# sensor_v4.net
KiCad netlist of a schematic drawn in EAGLE
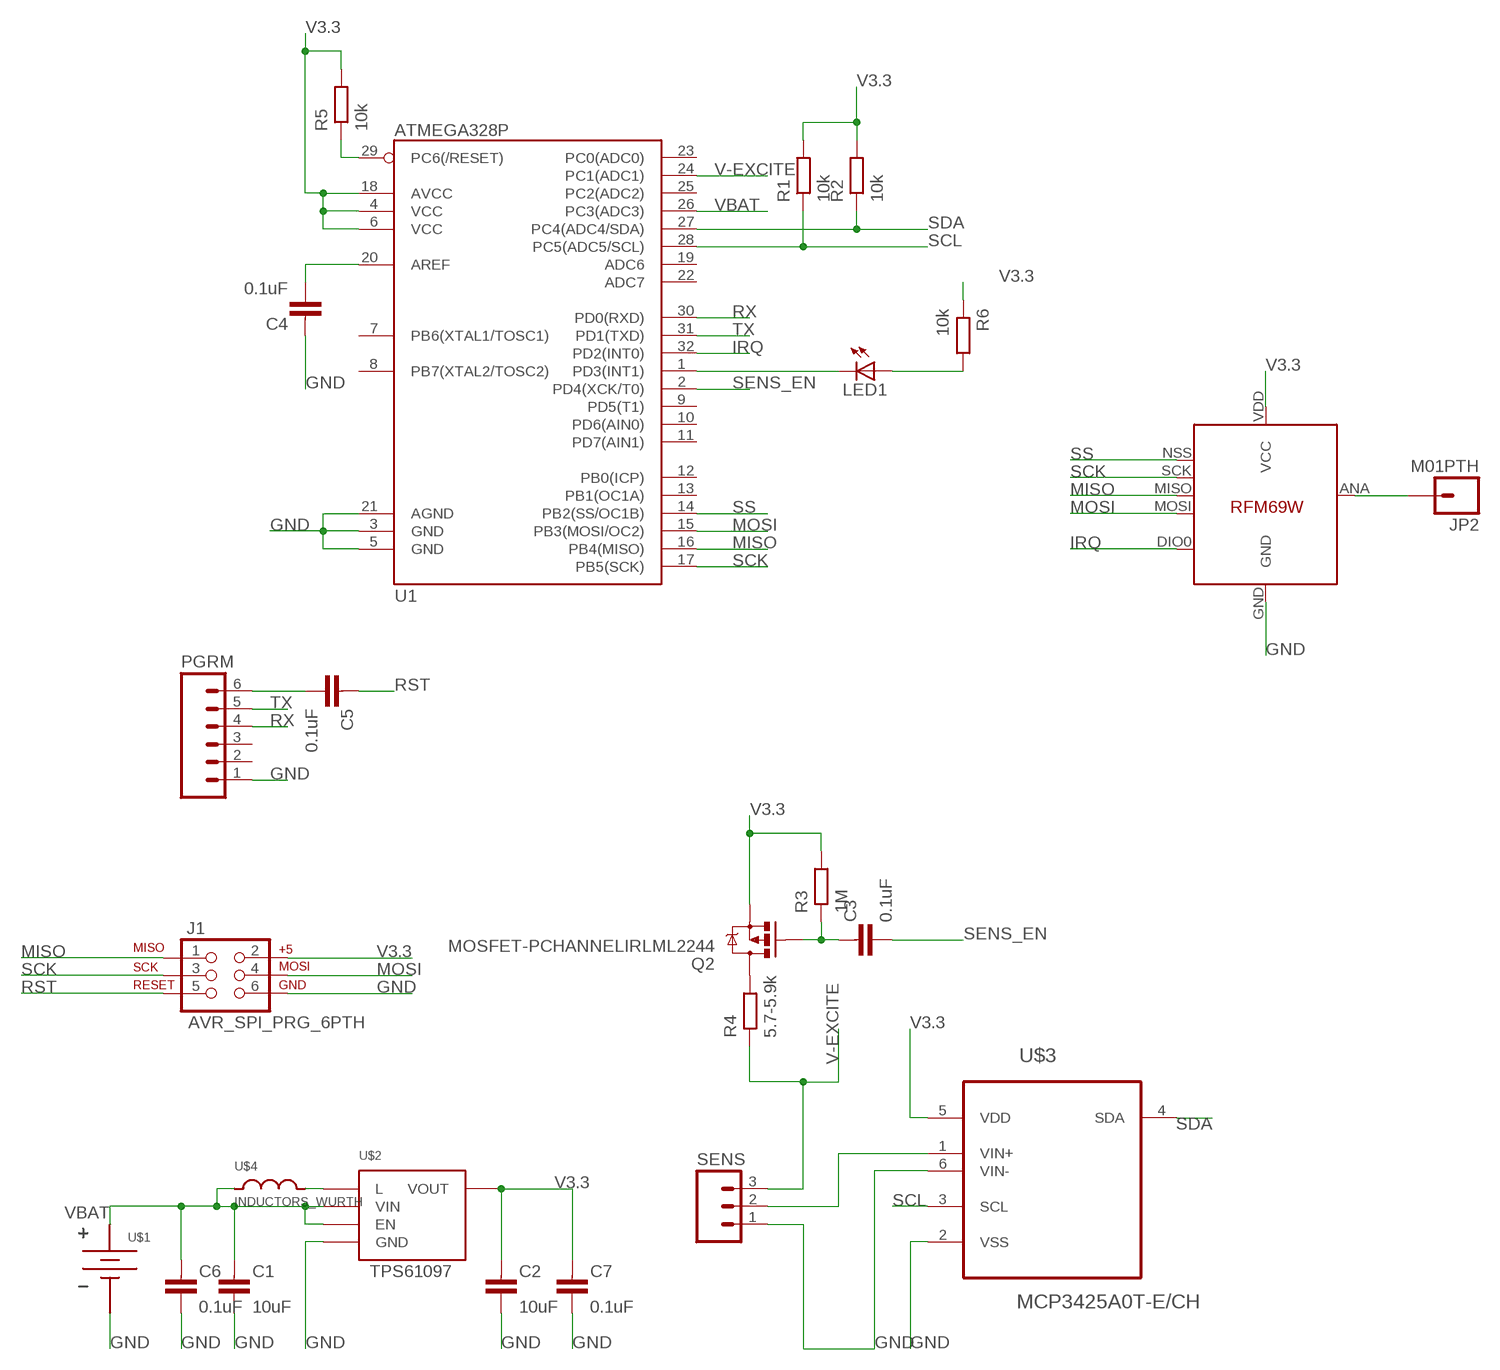
[diagram p0: schematic, sheet 1]

(export (version "E")
  (design (tool "Eeschema 10.0.6"))
  (components
    (comp (ref "C1")
      (value "10uF")
      (footprint "eagle-import:C0805-N")
      (libsource (lib "eagle-import") (part "CAPACITOR0805-N"))
    )
    (comp (ref "C2")
      (value "10uF")
      (footprint "eagle-import:C0805-N")
      (libsource (lib "eagle-import") (part "CAPACITOR0805-N"))
    )
    (comp (ref "C3")
      (value "0.1uF")
      (footprint "eagle-import:C0603-N")
      (libsource (lib "eagle-import") (part "CAPACITOR0603-N"))
    )
    (comp (ref "C4")
      (value "0.1uF")
      (footprint "eagle-import:C0603-N")
      (libsource (lib "eagle-import") (part "CAPACITOR0603-N"))
    )
    (comp (ref "C5")
      (value "0.1uF")
      (footprint "eagle-import:C0603-N")
      (libsource (lib "eagle-import") (part "CAPACITOR0603-N"))
    )
    (comp (ref "C6")
      (value "0.1uF")
      (footprint "eagle-import:C0603-N")
      (libsource (lib "eagle-import") (part "CAPACITOR0603-N"))
    )
    (comp (ref "C7")
      (value "0.1uF")
      (footprint "eagle-import:C0603-N")
      (libsource (lib "eagle-import") (part "CAPACITOR0603-N"))
    )
    (comp (ref "J1")
      (value "AVR_SPI_PRG_6PTH")
      (footprint "eagle-import:2X3")
      (libsource (lib "eagle-import") (part "AVR_SPI_PRG_6PTH"))
    )
    (comp (ref "JP2")
      (value "M01PTH")
      (footprint "eagle-import:1X01")
      (libsource (lib "eagle-import") (part "M01PTH"))
    )
    (comp (ref "LED1")
      (value "LED0603")
      (footprint "eagle-import:LED-0603")
      (libsource (lib "eagle-import") (part "LED0603"))
    )
    (comp (ref "PGRM")
      (value "M06LONGPADS")
      (footprint "eagle-import:1X06_LONGPADS")
      (libsource (lib "eagle-import") (part "M06LONGPADS"))
    )
    (comp (ref "Q2")
      (value "MOSFET-PCHANNELIRLML2244")
      (footprint "eagle-import:SOT23-3")
      (libsource (lib "eagle-import") (part "MOSFET-PCHANNELIRLML2244"))
    )
    (comp (ref "R1")
      (value "10k")
      (footprint "eagle-import:R0603-N")
      (libsource (lib "eagle-import") (part "RESISTOR0603-N"))
    )
    (comp (ref "R2")
      (value "10k")
      (footprint "eagle-import:R0603-N")
      (libsource (lib "eagle-import") (part "RESISTOR0603-N"))
    )
    (comp (ref "R3")
      (value "1M")
      (footprint "eagle-import:R0603-N")
      (libsource (lib "eagle-import") (part "RESISTOR0603-N"))
    )
    (comp (ref "R4")
      (value "5.7-5.9k")
      (footprint "eagle-import:R0603-N")
      (libsource (lib "eagle-import") (part "RESISTOR0603-N"))
    )
    (comp (ref "R5")
      (value "10k")
      (footprint "eagle-import:R0603-N")
      (libsource (lib "eagle-import") (part "RESISTOR0603-N"))
    )
    (comp (ref "R6")
      (value "10k")
      (footprint "eagle-import:R0603-N")
      (libsource (lib "eagle-import") (part "RESISTOR0603-N"))
    )
    (comp (ref "SENS")
      (value "M03PTH")
      (footprint "eagle-import:1X03")
      (libsource (lib "eagle-import") (part "M03PTH"))
    )
    (comp (ref "U$1")
      (value "KEYSTONEAAHOLDER_2CELL")
      (footprint "eagle-import:KEYSTONEAAHOLDER_2CELL")
      (libsource (lib "eagle-import") (part "KEYSTONEAAHOLDER_2CELL"))
    )
    (comp (ref "U$2")
      (value "TPS61097-33")
      (footprint "eagle-import:SOT23-5")
      (libsource (lib "eagle-import") (part "TPS61097-33"))
    )
    (comp (ref "U$3")
      (value "MCP3425A0T-E/CH")
      (footprint "eagle-import:SOT95P270X145-6N")
      (libsource (lib "eagle-import") (part "MCP3425A0T-E/CH"))
    )
    (comp (ref "U$4")
      (value "INDUCTORS_WURTH")
      (footprint "eagle-import:WURTH_10UH_650MA")
      (libsource (lib "eagle-import") (part "INDUCTORS_WURTH"))
    )
    (comp (ref "U$5")
      (value "RFM69")
      (footprint "eagle-import:RFM69W-MINPADS")
      (libsource (lib "eagle-import") (part "RFM69"))
    )
    (comp (ref "U1")
      (value "ATMEGA328P")
      (footprint "eagle-import:TQFP32-08")
      (libsource (lib "eagle-import") (part "ATMEGA328_SMT"))
    )
  )
  (nets
    (net (code "1") (name "/GND") (class "Default")
      (node (ref "C1") (pin "2") (pinfunction "2_2") (pintype "passive"))
      (node (ref "C2") (pin "2") (pinfunction "2_2") (pintype "passive"))
      (node (ref "C4") (pin "1") (pinfunction "1_1") (pintype "passive"))
      (node (ref "C6") (pin "2") (pinfunction "2_2") (pintype "passive"))
      (node (ref "C7") (pin "2") (pinfunction "2_2") (pintype "passive"))
      (node (ref "J1") (pin "6") (pinfunction "6_6") (pintype "passive"))
      (node (ref "PGRM") (pin "1") (pinfunction "1_1") (pintype "passive"))
      (node (ref "SENS") (pin "1") (pinfunction "1_1") (pintype "passive"))
      (node (ref "U$1") (pin "P$2") (pinfunction "GND_P$2") (pintype "bidirectional"))
      (node (ref "U$2") (pin "P$2") (pinfunction "GND_P$2") (pintype "power_in"))
      (node (ref "U$3") (pin "2") (pinfunction "VSS_2") (pintype "passive"))
      (node (ref "U$3") (pin "6") (pinfunction "VIN-_6") (pintype "input"))
      (node (ref "U$5") (pin "GND") (pinfunction "GND_GND") (pintype "power_in"))
      (node (ref "U1") (pin "21") (pinfunction "AGND_21") (pintype "bidirectional"))
      (node (ref "U1") (pin "3") (pinfunction "GND_3") (pintype "bidirectional"))
      (node (ref "U1") (pin "5") (pinfunction "GND_5") (pintype "bidirectional"))
    )
    (net (code "2") (name "/IRQ") (class "Default")
      (node (ref "U$5") (pin "DIO0") (pinfunction "DIO0_DIO0") (pintype "open_collector"))
      (node (ref "U1") (pin "32") (pinfunction "PD2(INT0)_32") (pintype "bidirectional"))
    )
    (net (code "3") (name "/MISO") (class "Default")
      (node (ref "J1") (pin "1") (pinfunction "1_1") (pintype "passive"))
      (node (ref "U$5") (pin "MISO") (pinfunction "MISO_MISO") (pintype "input"))
      (node (ref "U1") (pin "16") (pinfunction "PB4(MISO)_16") (pintype "bidirectional"))
    )
    (net (code "4") (name "/MOSI") (class "Default")
      (node (ref "J1") (pin "4") (pinfunction "4_4") (pintype "passive"))
      (node (ref "U$5") (pin "MOSI") (pinfunction "MOSI_MOSI") (pintype "output"))
      (node (ref "U1") (pin "15") (pinfunction "PB3(MOSI/OC2)_15") (pintype "bidirectional"))
    )
    (net (code "5") (name "/RST") (class "Default")
      (node (ref "C5") (pin "1") (pinfunction "1_1") (pintype "passive"))
      (node (ref "J1") (pin "5") (pinfunction "5_5") (pintype "passive"))
      (node (ref "R5") (pin "1") (pinfunction "P$1_1") (pintype "passive"))
      (node (ref "U1") (pin "29") (pinfunction "PC6(/RESET)_29") (pintype "bidirectional"))
    )
    (net (code "6") (name "/RX") (class "Default")
      (node (ref "PGRM") (pin "4") (pinfunction "4_4") (pintype "passive"))
      (node (ref "U1") (pin "30") (pinfunction "PD0(RXD)_30") (pintype "bidirectional"))
    )
    (net (code "7") (name "/SCK") (class "Default")
      (node (ref "J1") (pin "3") (pinfunction "3_3") (pintype "passive"))
      (node (ref "U$5") (pin "SCK") (pinfunction "SCK_SCK") (pintype "input"))
      (node (ref "U1") (pin "17") (pinfunction "PB5(SCK)_17") (pintype "bidirectional"))
    )
    (net (code "8") (name "/SCL") (class "Default")
      (node (ref "R1") (pin "1") (pinfunction "P$1_1") (pintype "passive"))
      (node (ref "U$3") (pin "3") (pinfunction "SCL_3") (pintype "input"))
      (node (ref "U1") (pin "28") (pinfunction "PC5(ADC5/SCL)_28") (pintype "bidirectional"))
    )
    (net (code "9") (name "/SDA") (class "Default")
      (node (ref "R2") (pin "1") (pinfunction "P$1_1") (pintype "passive"))
      (node (ref "U$3") (pin "4") (pinfunction "SDA_4") (pintype "bidirectional"))
      (node (ref "U1") (pin "27") (pinfunction "PC4(ADC4/SDA)_27") (pintype "bidirectional"))
    )
    (net (code "10") (name "/SENS_EN") (class "Default")
      (node (ref "C3") (pin "2") (pinfunction "2_2") (pintype "passive"))
      (node (ref "U1") (pin "2") (pinfunction "PD4(XCK/T0)_2") (pintype "bidirectional"))
    )
    (net (code "11") (name "/SS") (class "Default")
      (node (ref "U$5") (pin "NSS") (pinfunction "SEL_NSS") (pintype "input"))
      (node (ref "U1") (pin "14") (pinfunction "PB2(SS/OC1B)_14") (pintype "bidirectional"))
    )
    (net (code "12") (name "/TX") (class "Default")
      (node (ref "PGRM") (pin "5") (pinfunction "5_5") (pintype "passive"))
      (node (ref "U1") (pin "31") (pinfunction "PD1(TXD)_31") (pintype "bidirectional"))
    )
    (net (code "13") (name "/V-EXCITE") (class "Default")
      (node (ref "R4") (pin "1") (pinfunction "P$1_1") (pintype "passive"))
      (node (ref "SENS") (pin "3") (pinfunction "3_3") (pintype "passive"))
      (node (ref "U1") (pin "24") (pinfunction "PC1(ADC1)_24") (pintype "bidirectional"))
    )
    (net (code "14") (name "/V3.3") (class "Default")
      (node (ref "C2") (pin "1") (pinfunction "1_1") (pintype "passive"))
      (node (ref "C7") (pin "1") (pinfunction "1_1") (pintype "passive"))
      (node (ref "J1") (pin "2") (pinfunction "2_2") (pintype "passive"))
      (node (ref "Q2") (pin "2") (pinfunction "S_2") (pintype "passive"))
      (node (ref "R1") (pin "2") (pinfunction "P$2_2") (pintype "passive"))
      (node (ref "R2") (pin "2") (pinfunction "P$2_2") (pintype "passive"))
      (node (ref "R3") (pin "2") (pinfunction "P$2_2") (pintype "passive"))
      (node (ref "R5") (pin "2") (pinfunction "P$2_2") (pintype "passive"))
      (node (ref "R6") (pin "1") (pinfunction "P$1_1") (pintype "passive"))
      (node (ref "U$2") (pin "P$4") (pinfunction "VOUT_P$4") (pintype "power_in"))
      (node (ref "U$3") (pin "5") (pinfunction "VDD_5") (pintype "power_in"))
      (node (ref "U$5") (pin "VDD") (pinfunction "VCC_VDD") (pintype "power_in"))
      (node (ref "U1") (pin "18") (pinfunction "AVCC_18") (pintype "bidirectional"))
      (node (ref "U1") (pin "4") (pinfunction "VCC_4") (pintype "bidirectional"))
      (node (ref "U1") (pin "6") (pinfunction "VCC_6") (pintype "bidirectional"))
    )
    (net (code "15") (name "/VBAT") (class "Default")
      (node (ref "C1") (pin "1") (pinfunction "1_1") (pintype "passive"))
      (node (ref "C6") (pin "1") (pinfunction "1_1") (pintype "passive"))
      (node (ref "U$1") (pin "P$1") (pinfunction "VBAT_P$1") (pintype "bidirectional"))
      (node (ref "U$2") (pin "P$1") (pinfunction "VIN_P$1") (pintype "power_in"))
      (node (ref "U$2") (pin "P$3") (pinfunction "EN_P$3") (pintype "bidirectional"))
      (node (ref "U$4") (pin "P$2") (pinfunction "P$2_P$2") (pintype "passive"))
      (node (ref "U1") (pin "26") (pinfunction "PC3(ADC3)_26") (pintype "bidirectional"))
    )
    (net (code "16") (name "Net-(C5-Pad2)") (class "Default")
      (node (ref "C5") (pin "2") (pinfunction "2_2") (pintype "passive"))
      (node (ref "PGRM") (pin "6") (pinfunction "6_6") (pintype "passive"))
    )
    (net (code "17") (name "Net-(Q2-D)") (class "Default")
      (node (ref "Q2") (pin "3") (pinfunction "D_3") (pintype "passive"))
      (node (ref "R4") (pin "2") (pinfunction "P$2_2") (pintype "passive"))
    )
    (net (code "18") (name "Net-(Q2-G)") (class "Default")
      (node (ref "C3") (pin "1") (pinfunction "1_1") (pintype "passive"))
      (node (ref "Q2") (pin "1") (pinfunction "G_1") (pintype "passive"))
      (node (ref "R3") (pin "1") (pinfunction "P$1_1") (pintype "passive"))
    )
    (net (code "19") (name "Net-(R6-P$2)") (class "Default")
      (node (ref "LED1") (pin "A") (pinfunction "A_A") (pintype "passive"))
      (node (ref "R6") (pin "2") (pinfunction "P$2_2") (pintype "passive"))
    )
    (net (code "20") (name "Net-(U$2-L)") (class "Default")
      (node (ref "U$2") (pin "P$5") (pinfunction "L_P$5") (pintype "bidirectional"))
      (node (ref "U$4") (pin "P$1") (pinfunction "P$1_P$1") (pintype "passive"))
    )
    (net (code "21") (name "Net-(U$3-VIN+)") (class "Default")
      (node (ref "SENS") (pin "2") (pinfunction "2_2") (pintype "passive"))
      (node (ref "U$3") (pin "1") (pinfunction "VIN+_1") (pintype "input"))
    )
    (net (code "22") (name "Net-(U$5-ANT)") (class "Default")
      (node (ref "JP2") (pin "1") (pinfunction "1_1") (pintype "passive"))
      (node (ref "U$5") (pin "ANA") (pinfunction "ANT_ANA") (pintype "passive"))
    )
    (net (code "23") (name "Net-(U1-AREF)") (class "Default")
      (node (ref "C4") (pin "2") (pinfunction "2_2") (pintype "passive"))
      (node (ref "U1") (pin "20") (pinfunction "AREF_20") (pintype "bidirectional"))
    )
    (net (code "24") (name "Net-(U1-PD3(INT1))") (class "Default")
      (node (ref "LED1") (pin "C") (pinfunction "C_C") (pintype "passive"))
      (node (ref "U1") (pin "1") (pinfunction "PD3(INT1)_1") (pintype "bidirectional"))
    )
    (net (code "25") (name "unconnected-(PGRM-Pad2)") (class "Default")
      (node (ref "PGRM") (pin "2") (pinfunction "2_2") (pintype "passive"))
    )
    (net (code "26") (name "unconnected-(PGRM-Pad3)") (class "Default")
      (node (ref "PGRM") (pin "3") (pinfunction "3_3") (pintype "passive"))
    )
    (net (code "27") (name "unconnected-(U1-ADC6-Pad19)") (class "Default")
      (node (ref "U1") (pin "19") (pinfunction "ADC6_19") (pintype "bidirectional"))
    )
    (net (code "28") (name "unconnected-(U1-ADC7-Pad22)") (class "Default")
      (node (ref "U1") (pin "22") (pinfunction "ADC7_22") (pintype "bidirectional"))
    )
    (net (code "29") (name "unconnected-(U1-PB0(ICP)-Pad12)") (class "Default")
      (node (ref "U1") (pin "12") (pinfunction "PB0(ICP)_12") (pintype "bidirectional"))
    )
    (net (code "30") (name "unconnected-(U1-PB1(OC1A)-Pad13)") (class "Default")
      (node (ref "U1") (pin "13") (pinfunction "PB1(OC1A)_13") (pintype "bidirectional"))
    )
    (net (code "31") (name "unconnected-(U1-PB6(XTAL1{slash}TOSC1)-Pad7)") (class "Default")
      (node (ref "U1") (pin "7") (pinfunction "PB6(XTAL1/TOSC1)_7") (pintype "bidirectional"))
    )
    (net (code "32") (name "unconnected-(U1-PB7(XTAL2{slash}TOSC2)-Pad8)") (class "Default")
      (node (ref "U1") (pin "8") (pinfunction "PB7(XTAL2/TOSC2)_8") (pintype "bidirectional"))
    )
    (net (code "33") (name "unconnected-(U1-PC0(ADC0)-Pad23)") (class "Default")
      (node (ref "U1") (pin "23") (pinfunction "PC0(ADC0)_23") (pintype "bidirectional"))
    )
    (net (code "34") (name "unconnected-(U1-PC2(ADC2)-Pad25)") (class "Default")
      (node (ref "U1") (pin "25") (pinfunction "PC2(ADC2)_25") (pintype "bidirectional"))
    )
    (net (code "35") (name "unconnected-(U1-PD5(T1)-Pad9)") (class "Default")
      (node (ref "U1") (pin "9") (pinfunction "PD5(T1)_9") (pintype "bidirectional"))
    )
    (net (code "36") (name "unconnected-(U1-PD6(AIN0)-Pad10)") (class "Default")
      (node (ref "U1") (pin "10") (pinfunction "PD6(AIN0)_10") (pintype "bidirectional"))
    )
    (net (code "37") (name "unconnected-(U1-PD7(AIN1)-Pad11)") (class "Default")
      (node (ref "U1") (pin "11") (pinfunction "PD7(AIN1)_11") (pintype "bidirectional"))
    )
  )
)
